# NotSoSmartWatch-BASIC-TOP.net
KiCad netlist of a schematic drawn in EAGLE
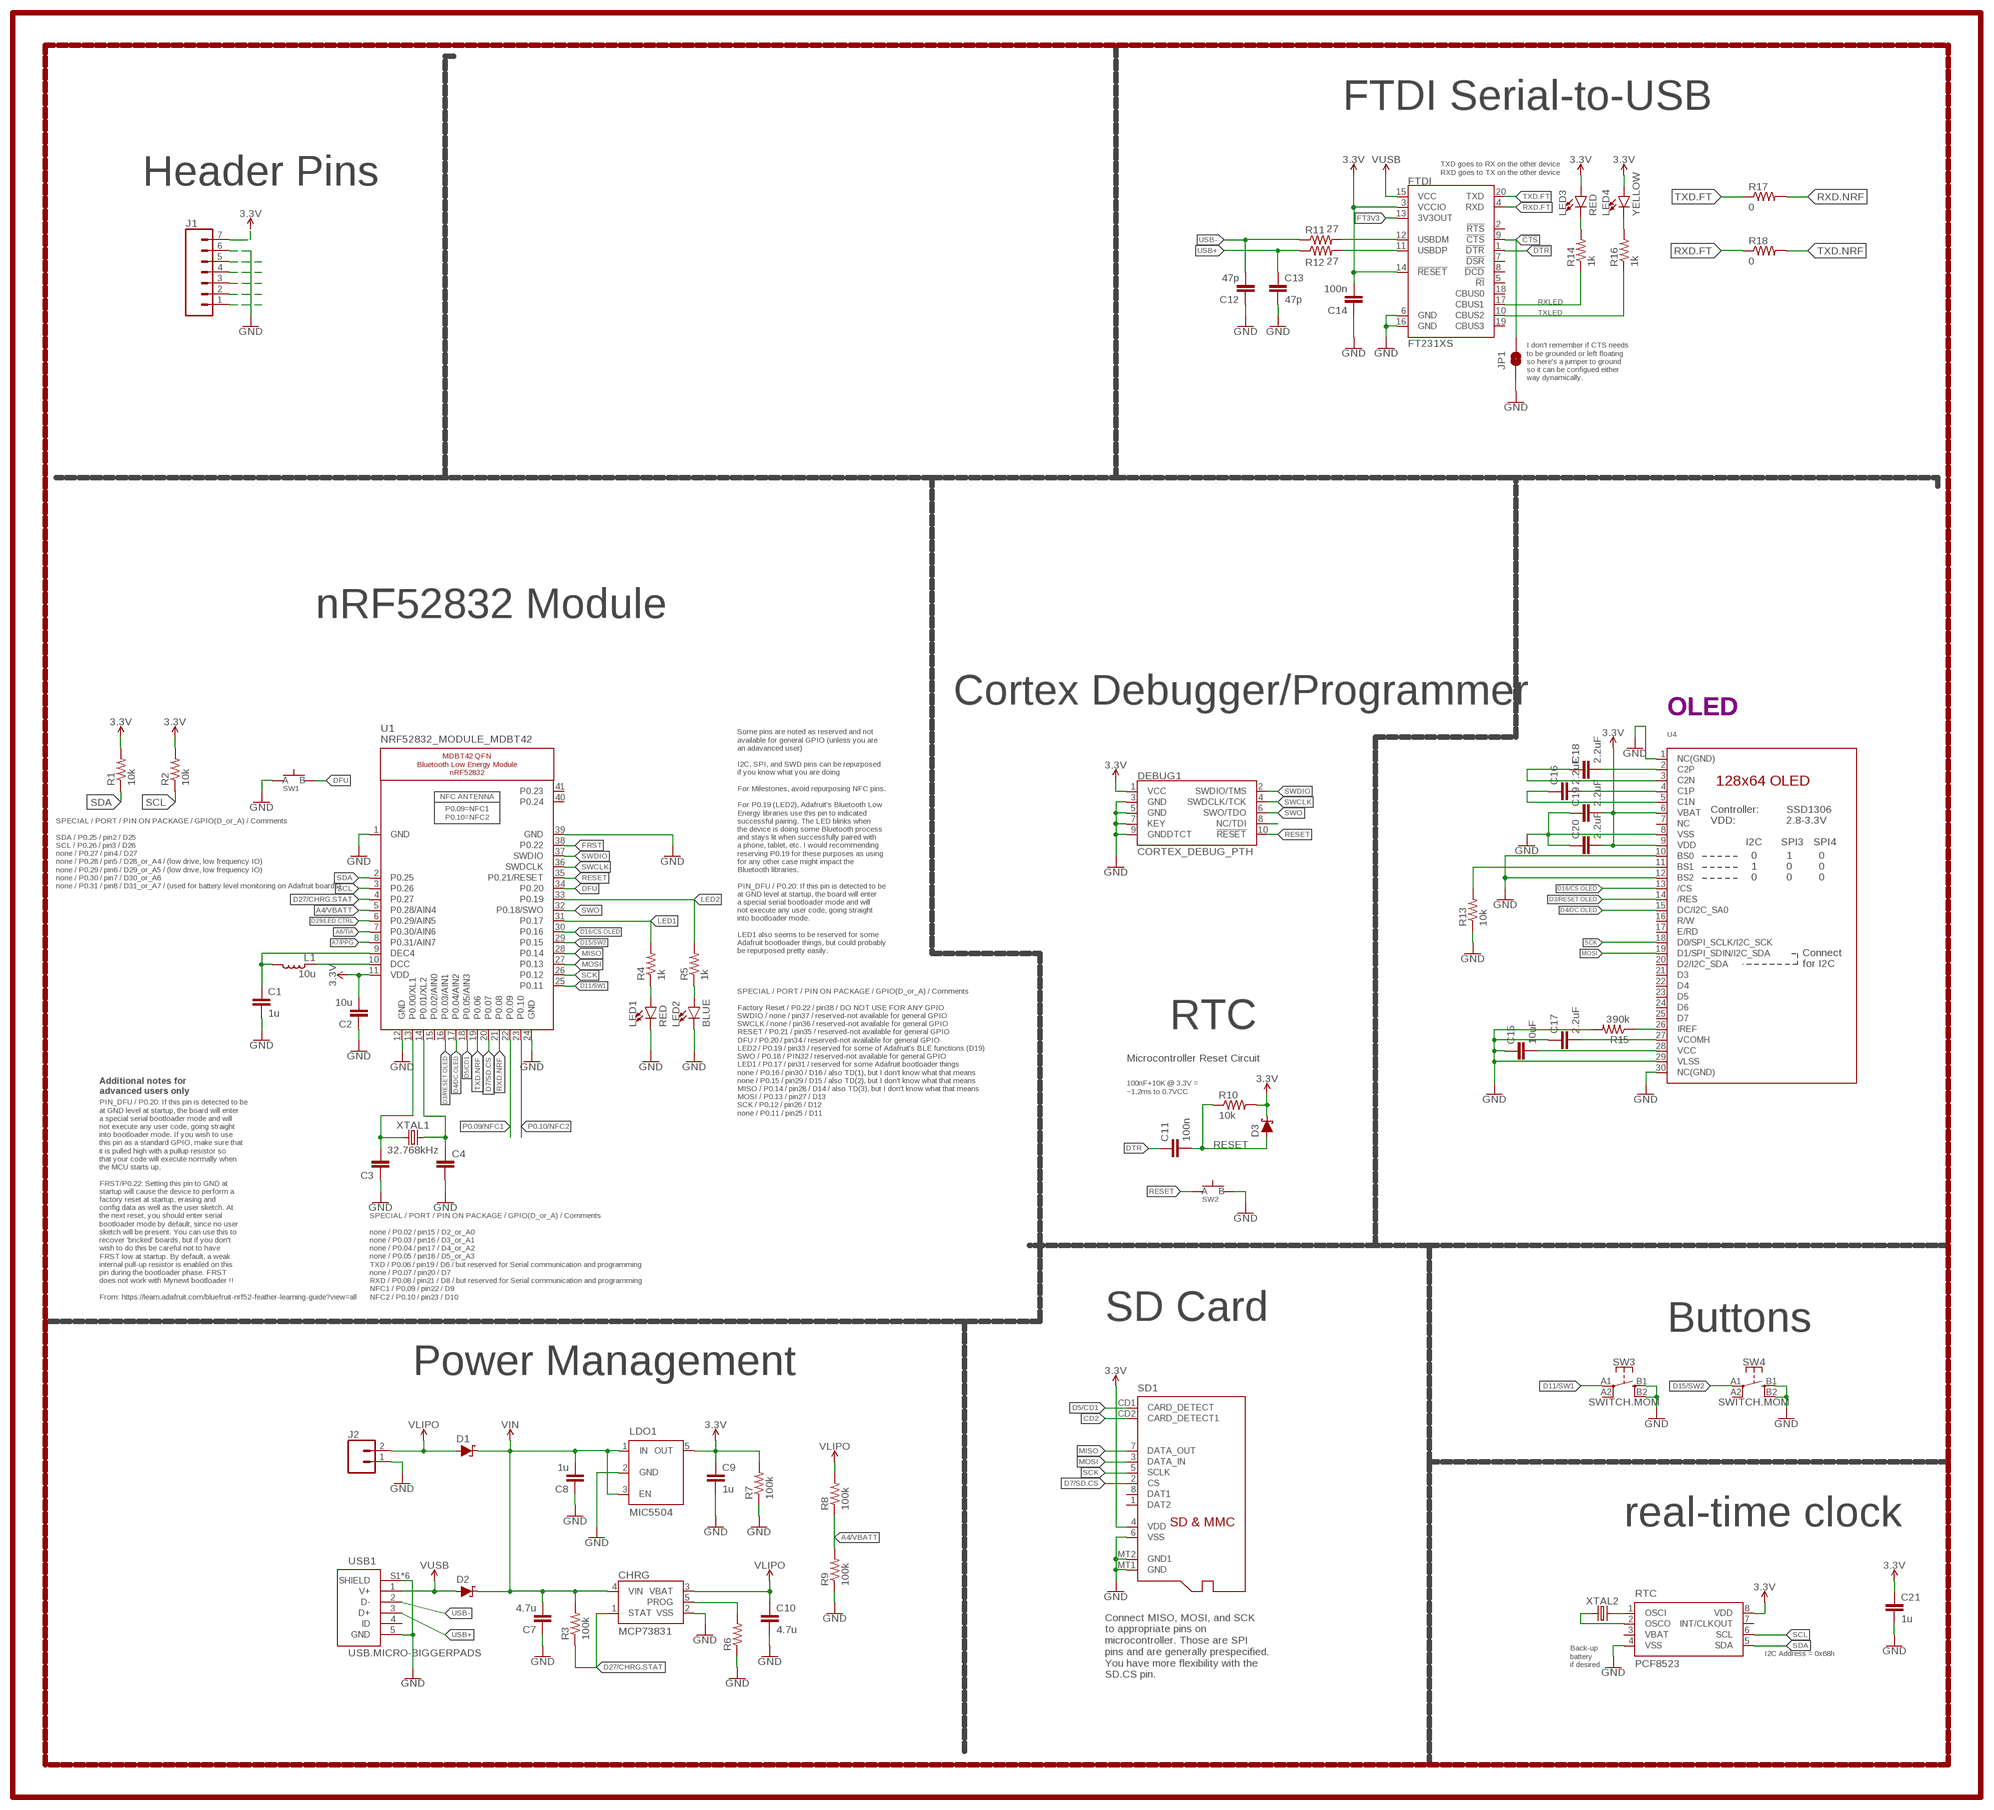
[diagram p0: schematic, sheet 1]

(export (version "E")
  (design (tool "Eeschema 10.0.6"))
  (components
    (comp (ref "C1")
      (value "1u")
      (footprint "eagle-import:C0603")
      (libsource (lib "eagle-import") (part "CAPACITOR0603"))
    )
    (comp (ref "C2")
      (value "10u")
      (footprint "eagle-import:C0805")
      (libsource (lib "eagle-import") (part "CAPACITOR0805"))
    )
    (comp (ref "C3")
      (value "CAPACITOR0603")
      (footprint "eagle-import:C0603")
      (libsource (lib "eagle-import") (part "CAPACITOR0603"))
    )
    (comp (ref "C4")
      (value "CAPACITOR0603")
      (footprint "eagle-import:C0603")
      (libsource (lib "eagle-import") (part "CAPACITOR0603"))
    )
    (comp (ref "C7")
      (value "4.7u")
      (footprint "eagle-import:C0603")
      (libsource (lib "eagle-import") (part "CAPACITOR0603"))
    )
    (comp (ref "C8")
      (value "1u")
      (footprint "eagle-import:C0603")
      (libsource (lib "eagle-import") (part "CAPACITOR0603"))
    )
    (comp (ref "C9")
      (value "1u")
      (footprint "eagle-import:C0603")
      (libsource (lib "eagle-import") (part "CAPACITOR0603"))
    )
    (comp (ref "C10")
      (value "4.7u")
      (footprint "eagle-import:C0603")
      (libsource (lib "eagle-import") (part "CAPACITOR0603"))
    )
    (comp (ref "C11")
      (value "100n")
      (footprint "eagle-import:C0603")
      (libsource (lib "eagle-import") (part "CAPACITOR0603"))
    )
    (comp (ref "C12")
      (value "47p")
      (footprint "eagle-import:C0603")
      (fields (field (name "SPICEPREFIX") "C"))
      (libsource (lib "eagle-import") (part "CAPACITOR0603"))
    )
    (comp (ref "C13")
      (value "47p")
      (footprint "eagle-import:C0603")
      (fields (field (name "SPICEPREFIX") "C"))
      (libsource (lib "eagle-import") (part "CAPACITOR0603"))
    )
    (comp (ref "C14")
      (value "100n")
      (footprint "eagle-import:C0603")
      (fields (field (name "SPICEPREFIX") "C"))
      (libsource (lib "eagle-import") (part "CAPACITOR0603"))
    )
    (comp (ref "C15")
      (value "10uF")
      (footprint "eagle-import:C0603")
      (libsource (lib "eagle-import") (part "CAPACITOR0603"))
    )
    (comp (ref "C16")
      (value "2.2uF")
      (footprint "eagle-import:C0402")
      (libsource (lib "eagle-import") (part "CAPACITOR0402"))
    )
    (comp (ref "C17")
      (value "2.2uF")
      (footprint "eagle-import:C0402")
      (libsource (lib "eagle-import") (part "CAPACITOR0402"))
    )
    (comp (ref "C18")
      (value "2.2uF")
      (footprint "eagle-import:C0402")
      (libsource (lib "eagle-import") (part "CAPACITOR0402"))
    )
    (comp (ref "C19")
      (value "2.2uF")
      (footprint "eagle-import:C0402")
      (libsource (lib "eagle-import") (part "CAPACITOR0402"))
    )
    (comp (ref "C20")
      (value "2.2uF")
      (footprint "eagle-import:C0402")
      (libsource (lib "eagle-import") (part "CAPACITOR0402"))
    )
    (comp (ref "C21")
      (value "1u")
      (footprint "eagle-import:C0603")
      (libsource (lib "eagle-import") (part "CAPACITOR0603"))
    )
    (comp (ref "CHRG")
      (value "MCP73831")
      (footprint "eagle-import:SOT23-5")
      (libsource (lib "eagle-import") (part "MCP73831"))
    )
    (comp (ref "D1")
      (value "SCHOTTKY-USC")
      (footprint "eagle-import:USC")
      (libsource (lib "eagle-import") (part "SCHOTTKY-USC"))
    )
    (comp (ref "D2")
      (value "SCHOTTKY-USC")
      (footprint "eagle-import:USC")
      (libsource (lib "eagle-import") (part "SCHOTTKY-USC"))
    )
    (comp (ref "D3")
      (value "SCHOTTKY-USC")
      (footprint "eagle-import:USC")
      (libsource (lib "eagle-import") (part "SCHOTTKY-USC"))
    )
    (comp (ref "DEBUG1")
      (value "CORTEX_DEBUG_PTH")
      (footprint "eagle-import:2X5-PTH-1.27MM")
      (libsource (lib "eagle-import") (part "CORTEX_DEBUG_PTH"))
    )
    (comp (ref "FTDI")
      (value "FT231XS")
      (footprint "eagle-import:SSOP20_L")
      (fields (field (name "SPICEPREFIX") "X"))
      (libsource (lib "eagle-import") (part "FT231XS"))
    )
    (comp (ref "J1")
      (value "CONN_07-1.27MM")
      (footprint "eagle-import:1X07_1.27MM")
      (libsource (lib "eagle-import") (part "CONN_07-1.27MM"))
    )
    (comp (ref "J2")
      (value "CONN_02")
      (footprint "eagle-import:1X02")
      (libsource (lib "eagle-import") (part "CONN_02"))
    )
    (comp (ref "JP1")
      (value "JUMPER-SMT_2_NO_SILK")
      (footprint "eagle-import:SMT-JUMPER_2_NO_SILK")
      (fields (field (name "SPICEPREFIX") "B"))
      (libsource (lib "eagle-import") (part "JUMPER-SMT_2_NO_SILK"))
    )
    (comp (ref "L1")
      (value "10u")
      (footprint "eagle-import:L0603")
      (libsource (lib "eagle-import") (part "INDUCTOR0603"))
    )
    (comp (ref "LDO1")
      (value "MIC5504")
      (footprint "eagle-import:SOT23-5")
      (libsource (lib "eagle-import") (part "MIC5504"))
    )
    (comp (ref "LED1")
      (value "RED")
      (footprint "eagle-import:LED-0603")
      (libsource (lib "eagle-import") (part "LED0603"))
    )
    (comp (ref "LED2")
      (value "BLUE")
      (footprint "eagle-import:LED-0603")
      (libsource (lib "eagle-import") (part "LED0603"))
    )
    (comp (ref "LED3")
      (value "RED")
      (footprint "eagle-import:LED-0603")
      (fields (field (name "SPICEPREFIX") "L"))
      (libsource (lib "eagle-import") (part "LED0603"))
    )
    (comp (ref "LED4")
      (value "YELLOW")
      (footprint "eagle-import:LED-0603")
      (fields (field (name "SPICEPREFIX") "L"))
      (libsource (lib "eagle-import") (part "LED0603"))
    )
    (comp (ref "R1")
      (value "10k")
      (footprint "eagle-import:R0603")
      (libsource (lib "eagle-import") (part "RESISTOR0603"))
    )
    (comp (ref "R2")
      (value "10k")
      (footprint "eagle-import:R0603")
      (libsource (lib "eagle-import") (part "RESISTOR0603"))
    )
    (comp (ref "R3")
      (value "100k")
      (footprint "eagle-import:R0603")
      (libsource (lib "eagle-import") (part "RESISTOR0603"))
    )
    (comp (ref "R4")
      (value "1k")
      (footprint "eagle-import:R0603")
      (libsource (lib "eagle-import") (part "RESISTOR0603"))
    )
    (comp (ref "R5")
      (value "1k")
      (footprint "eagle-import:R0603")
      (libsource (lib "eagle-import") (part "RESISTOR0603"))
    )
    (comp (ref "R6")
      (value "RESISTOR0603")
      (footprint "eagle-import:R0603")
      (libsource (lib "eagle-import") (part "RESISTOR0603"))
    )
    (comp (ref "R7")
      (value "100k")
      (footprint "eagle-import:R0603")
      (libsource (lib "eagle-import") (part "RESISTOR0603"))
    )
    (comp (ref "R8")
      (value "100k")
      (footprint "eagle-import:R0603")
      (libsource (lib "eagle-import") (part "RESISTOR0603"))
    )
    (comp (ref "R9")
      (value "100k")
      (footprint "eagle-import:R0603")
      (libsource (lib "eagle-import") (part "RESISTOR0603"))
    )
    (comp (ref "R10")
      (value "10k")
      (footprint "eagle-import:R0603")
      (libsource (lib "eagle-import") (part "RESISTOR0603"))
    )
    (comp (ref "R11")
      (value "27")
      (footprint "eagle-import:R0603")
      (fields (field (name "SPICEPREFIX") "R"))
      (libsource (lib "eagle-import") (part "RESISTOR0603"))
    )
    (comp (ref "R12")
      (value "27")
      (footprint "eagle-import:R0603")
      (fields (field (name "SPICEPREFIX") "R"))
      (libsource (lib "eagle-import") (part "RESISTOR0603"))
    )
    (comp (ref "R13")
      (value "10k")
      (footprint "eagle-import:R0603")
      (libsource (lib "eagle-import") (part "RESISTOR0603"))
    )
    (comp (ref "R14")
      (value "1k")
      (footprint "eagle-import:R0603")
      (fields (field (name "SPICEPREFIX") "R"))
      (libsource (lib "eagle-import") (part "RESISTOR0603"))
    )
    (comp (ref "R15")
      (value "390k")
      (footprint "eagle-import:R0603")
      (libsource (lib "eagle-import") (part "RESISTOR0603"))
    )
    (comp (ref "R16")
      (value "1k")
      (footprint "eagle-import:R0603")
      (fields (field (name "SPICEPREFIX") "R"))
      (libsource (lib "eagle-import") (part "RESISTOR0603"))
    )
    (comp (ref "R17")
      (value "0")
      (footprint "eagle-import:R0603")
      (libsource (lib "eagle-import") (part "RESISTOR0603"))
    )
    (comp (ref "R18")
      (value "0")
      (footprint "eagle-import:R0603")
      (libsource (lib "eagle-import") (part "RESISTOR0603"))
    )
    (comp (ref "RTC")
      (value "PCF8523")
      (footprint "eagle-import:SO8")
      (libsource (lib "eagle-import") (part "PCF8523"))
    )
    (comp (ref "SD1")
      (value "MICROSD")
      (footprint "eagle-import:MICROSD")
      (libsource (lib "eagle-import") (part "MICROSD"))
    )
    (comp (ref "SW1")
      (value "SPST-PTS830GG140-COPY.1-3")
      (footprint "eagle-import:BUTTON-GULLWING")
      (libsource (lib "eagle-import") (part "SPST-PTS830GG140-COPY.1-3"))
    )
    (comp (ref "SW2")
      (value "SPST-PTS830GG140-COPY.1-3")
      (footprint "eagle-import:BUTTON-GULLWING")
      (libsource (lib "eagle-import") (part "SPST-PTS830GG140-COPY.1-3"))
    )
    (comp (ref "SW3")
      (value "SWITCH.MOM")
      (footprint "eagle-import:TACTILE_SWITCH_SMD_6.2MM_TALL")
      (libsource (lib "eagle-import") (part "SWITCH.MOM"))
    )
    (comp (ref "SW4")
      (value "SWITCH.MOM")
      (footprint "eagle-import:TACTILE_SWITCH_SMD_6.2MM_TALL")
      (libsource (lib "eagle-import") (part "SWITCH.MOM"))
    )
    (comp (ref "U1")
      (value "NRF52832_MODULE_MDBT42")
      (footprint "eagle-import:BLE_MODULE_RAYTAC_MDBT42")
      (libsource (lib "eagle-import") (part "NRF52832_MODULE_MDBT42"))
    )
    (comp (ref "U4")
      (value "DISP_OLED_UG-2864HSWEG01-NO-WRAPAROUND")
      (footprint "eagle-import:UG-2864HSWEG01_0.96IN_NO-WRAPAROUND")
      (libsource (lib "eagle-import") (part "DISP_OLED_UG-2864HSWEG01-NO-WRAPAROUND"))
    )
    (comp (ref "USB1")
      (value "USB.MICRO-BIGGERPADS")
      (footprint "eagle-import:USB-MICRO-01.BIGGERPADS")
      (libsource (lib "eagle-import") (part "USB.MICRO-BIGGERPADS"))
    )
    (comp (ref "XTAL1")
      (value "32.768kHz")
      (footprint "eagle-import:2-SMD.NOLEAD.2.0MMTO1.2MM")
      (libsource (lib "eagle-import") (part "CRYSTALECS-.327-12.5-12-C-TR"))
    )
    (comp (ref "XTAL2")
      (value "32.7680kHz")
      (footprint "eagle-import:2-SMD.NOLEAD.2.0MMTO1.2MM")
      (fields (field (name "FREQ") "32.7680KHZ"))
      (libsource (lib "eagle-import") (part "CRYSTALECS-.327-12.5-12-C-TR"))
    )
  )
  (nets
    (net (code "1") (name "/RXLED") (class "Default")
      (node (ref "FTDI") (pin "17") (pinfunction "CBUS1_17") (pintype "bidirectional"))
      (node (ref "R14") (pin "1") (pinfunction "1_1") (pintype "passive"))
    )
    (net (code "2") (name "/TXLED") (class "Default")
      (node (ref "FTDI") (pin "10") (pinfunction "CBUS2_10") (pintype "bidirectional"))
      (node (ref "R16") (pin "1") (pinfunction "1_1") (pintype "passive"))
    )
    (net (code "3") (name "/VBAT") (class "Default")
      (node (ref "RTC") (pin "3") (pinfunction "VBAT_3") (pintype "power_in"))
    )
    (net (code "4") (name "/~{CTS}") (class "Default")
      (node (ref "FTDI") (pin "9") (pinfunction "~{CTS}_9") (pintype "bidirectional"))
      (node (ref "JP1") (pin "2") (pinfunction "2_2") (pintype "passive"))
    )
    (net (code "5") (name "/~{DTR}") (class "Default")
      (node (ref "FTDI") (pin "1") (pinfunction "~{DTR}_1") (pintype "bidirectional"))
    )
    (net (code "6") (name "3.3V") (class "Default")
      (node (ref "C14") (pin "2") (pinfunction "2_2") (pintype "passive"))
      (node (ref "C19") (pin "2") (pinfunction "2_2") (pintype "passive"))
      (node (ref "C2") (pin "2") (pinfunction "2_2") (pintype "passive"))
      (node (ref "C20") (pin "2") (pinfunction "2_2") (pintype "passive"))
      (node (ref "C21") (pin "1") (pinfunction "1_1") (pintype "passive"))
      (node (ref "C9") (pin "1") (pinfunction "1_1") (pintype "passive"))
      (node (ref "D3") (pin "-") (pinfunction "C_-") (pintype "passive"))
      (node (ref "DEBUG1") (pin "1") (pinfunction "VCC_1") (pintype "bidirectional"))
      (node (ref "FTDI") (pin "14") (pinfunction "~{RESET}_14") (pintype "bidirectional"))
      (node (ref "FTDI") (pin "3") (pinfunction "VCCIO_3") (pintype "bidirectional"))
      (node (ref "J1") (pin "7") (pinfunction "7_7") (pintype "passive"))
      (node (ref "LDO1") (pin "5") (pinfunction "OUT_5") (pintype "bidirectional"))
      (node (ref "LED3") (pin "A") (pinfunction "A_A") (pintype "passive"))
      (node (ref "LED4") (pin "A") (pinfunction "A_A") (pintype "passive"))
      (node (ref "R1") (pin "2") (pinfunction "2_2") (pintype "passive"))
      (node (ref "R10") (pin "2") (pinfunction "2_2") (pintype "passive"))
      (node (ref "R2") (pin "2") (pinfunction "2_2") (pintype "passive"))
      (node (ref "R7") (pin "2") (pinfunction "2_2") (pintype "passive"))
      (node (ref "RTC") (pin "8") (pinfunction "VDD_8") (pintype "power_in"))
      (node (ref "SD1") (pin "4") (pinfunction "VDD_4") (pintype "power_in"))
      (node (ref "U1") (pin "11") (pinfunction "VDD_11") (pintype "bidirectional"))
      (node (ref "U4") (pin "6") (pinfunction "VBAT_6") (pintype "input"))
      (node (ref "U4") (pin "9") (pinfunction "VDD_9") (pintype "power_in"))
    )
    (net (code "7") (name "A4{slash}VBATT") (class "Default")
      (node (ref "R8") (pin "1") (pinfunction "1_1") (pintype "passive"))
      (node (ref "R9") (pin "2") (pinfunction "2_2") (pintype "passive"))
      (node (ref "U1") (pin "5") (pinfunction "P0.28/AIN4_5") (pintype "bidirectional"))
    )
    (net (code "8") (name "A6{slash}TIA") (class "Default")
      (node (ref "U1") (pin "7") (pinfunction "P0.30/AIN6_7") (pintype "bidirectional"))
    )
    (net (code "9") (name "A7{slash}PPG") (class "Default")
      (node (ref "U1") (pin "8") (pinfunction "P0.31/AIN7_8") (pintype "bidirectional"))
    )
    (net (code "10") (name "CD2") (class "Default")
      (node (ref "SD1") (pin "CD2") (pinfunction "CARD_DETECT1_CD2") (pintype "passive"))
    )
    (net (code "11") (name "D3{slash}RESET.OLED") (class "Default")
      (node (ref "U1") (pin "16") (pinfunction "P0.03/AIN1_16") (pintype "bidirectional"))
      (node (ref "U4") (pin "14") (pinfunction "/RES_14") (pintype "input"))
    )
    (net (code "12") (name "D4{slash}DC.OLED") (class "Default")
      (node (ref "U1") (pin "17") (pinfunction "P0.04/AIN2_17") (pintype "bidirectional"))
      (node (ref "U4") (pin "15") (pinfunction "DC/I2C_SA0_15") (pintype "input"))
    )
    (net (code "13") (name "D5{slash}CD1") (class "Default")
      (node (ref "SD1") (pin "CD1") (pinfunction "CARD_DETECT_CD1") (pintype "passive"))
      (node (ref "U1") (pin "18") (pinfunction "P0.05/AIN3_18") (pintype "bidirectional"))
    )
    (net (code "14") (name "D7{slash}SD.CS") (class "Default")
      (node (ref "SD1") (pin "2") (pinfunction "CS_2") (pintype "input"))
      (node (ref "U1") (pin "20") (pinfunction "P0.07_20") (pintype "bidirectional"))
    )
    (net (code "15") (name "D11{slash}SW1") (class "Default")
      (node (ref "SW3") (pin "A1") (pinfunction "1_A1") (pintype "passive"))
      (node (ref "U1") (pin "25") (pinfunction "P0.11_25") (pintype "bidirectional"))
    )
    (net (code "16") (name "D15{slash}SW2") (class "Default")
      (node (ref "SW4") (pin "A1") (pinfunction "1_A1") (pintype "passive"))
      (node (ref "U1") (pin "29") (pinfunction "P0.15_29") (pintype "bidirectional"))
    )
    (net (code "17") (name "D16{slash}CS.OLED") (class "Default")
      (node (ref "U1") (pin "30") (pinfunction "P0.16_30") (pintype "bidirectional"))
      (node (ref "U4") (pin "13") (pinfunction "/CS_13") (pintype "input"))
    )
    (net (code "18") (name "D27{slash}CHRG.STAT") (class "Default")
      (node (ref "CHRG") (pin "1") (pinfunction "STAT_1") (pintype "output"))
      (node (ref "R3") (pin "1") (pinfunction "1_1") (pintype "passive"))
      (node (ref "U1") (pin "4") (pinfunction "P0.27_4") (pintype "bidirectional"))
    )
    (net (code "19") (name "D29{slash}LED.CTRL") (class "Default")
      (node (ref "U1") (pin "6") (pinfunction "P0.29/AIN5_6") (pintype "bidirectional"))
    )
    (net (code "20") (name "DFU") (class "Default")
      (node (ref "SW1") (pin "3") (pinfunction "B_3") (pintype "bidirectional"))
      (node (ref "U1") (pin "34") (pinfunction "P0.20_34") (pintype "bidirectional"))
    )
    (net (code "21") (name "DTR") (class "Default")
      (node (ref "C11") (pin "1") (pinfunction "1_1") (pintype "passive"))
    )
    (net (code "22") (name "FRST") (class "Default")
      (node (ref "U1") (pin "38") (pinfunction "P0.22_38") (pintype "bidirectional"))
    )
    (net (code "23") (name "FT3V3") (class "Default")
      (node (ref "FTDI") (pin "13") (pinfunction "3V3OUT_13") (pintype "bidirectional"))
    )
    (net (code "24") (name "GND") (class "Default")
      (node (ref "C1") (pin "2") (pinfunction "2_2") (pintype "passive"))
      (node (ref "C10") (pin "2") (pinfunction "2_2") (pintype "passive"))
      (node (ref "C12") (pin "1") (pinfunction "1_1") (pintype "passive"))
      (node (ref "C13") (pin "2") (pinfunction "2_2") (pintype "passive"))
      (node (ref "C14") (pin "1") (pinfunction "1_1") (pintype "passive"))
      (node (ref "C15") (pin "1") (pinfunction "1_1") (pintype "passive"))
      (node (ref "C17") (pin "1") (pinfunction "1_1") (pintype "passive"))
      (node (ref "C19") (pin "1") (pinfunction "1_1") (pintype "passive"))
      (node (ref "C2") (pin "1") (pinfunction "1_1") (pintype "passive"))
      (node (ref "C20") (pin "1") (pinfunction "1_1") (pintype "passive"))
      (node (ref "C21") (pin "2") (pinfunction "2_2") (pintype "passive"))
      (node (ref "C3") (pin "1") (pinfunction "1_1") (pintype "passive"))
      (node (ref "C4") (pin "2") (pinfunction "2_2") (pintype "passive"))
      (node (ref "C7") (pin "1") (pinfunction "1_1") (pintype "passive"))
      (node (ref "C8") (pin "1") (pinfunction "1_1") (pintype "passive"))
      (node (ref "C9") (pin "2") (pinfunction "2_2") (pintype "passive"))
      (node (ref "CHRG") (pin "2") (pinfunction "VSS_2") (pintype "power_in"))
      (node (ref "DEBUG1") (pin "3") (pinfunction "GND_3") (pintype "bidirectional"))
      (node (ref "DEBUG1") (pin "5") (pinfunction "GND_5") (pintype "bidirectional"))
      (node (ref "DEBUG1") (pin "7") (pinfunction "KEY_7") (pintype "bidirectional"))
      (node (ref "DEBUG1") (pin "9") (pinfunction "GNDDTCT_9") (pintype "bidirectional"))
      (node (ref "FTDI") (pin "16") (pinfunction "GND_16") (pintype "bidirectional"))
      (node (ref "FTDI") (pin "6") (pinfunction "GND_6") (pintype "bidirectional"))
      (node (ref "J1") (pin "6") (pinfunction "6_6") (pintype "passive"))
      (node (ref "J2") (pin "1") (pinfunction "1_1") (pintype "passive"))
      (node (ref "JP1") (pin "1") (pinfunction "1_1") (pintype "passive"))
      (node (ref "LDO1") (pin "2") (pinfunction "GND_2") (pintype "bidirectional"))
      (node (ref "LED1") (pin "C") (pinfunction "C_C") (pintype "passive"))
      (node (ref "LED2") (pin "C") (pinfunction "C_C") (pintype "passive"))
      (node (ref "R13") (pin "1") (pinfunction "1_1") (pintype "passive"))
      (node (ref "R15") (pin "2") (pinfunction "2_2") (pintype "passive"))
      (node (ref "R6") (pin "1") (pinfunction "1_1") (pintype "passive"))
      (node (ref "R7") (pin "1") (pinfunction "1_1") (pintype "passive"))
      (node (ref "R9") (pin "1") (pinfunction "1_1") (pintype "passive"))
      (node (ref "RTC") (pin "4") (pinfunction "VSS_4") (pintype "power_in"))
      (node (ref "SD1") (pin "6") (pinfunction "VSS_6") (pintype "power_in"))
      (node (ref "SD1") (pin "MT1") (pinfunction "GND_MT1") (pintype "power_in"))
      (node (ref "SD1") (pin "MT2") (pinfunction "GND1_MT2") (pintype "power_in"))
      (node (ref "SW1") (pin "1") (pinfunction "A_1") (pintype "bidirectional"))
      (node (ref "SW2") (pin "3") (pinfunction "B_3") (pintype "bidirectional"))
      (node (ref "SW3") (pin "B1") (pinfunction "3_B1") (pintype "passive"))
      (node (ref "SW3") (pin "B2") (pinfunction "4_B2") (pintype "passive"))
      (node (ref "SW4") (pin "B1") (pinfunction "3_B1") (pintype "passive"))
      (node (ref "SW4") (pin "B2") (pinfunction "4_B2") (pintype "passive"))
      (node (ref "U1") (pin "1") (pinfunction "GND_1") (pintype "bidirectional"))
      (node (ref "U1") (pin "12") (pinfunction "GND_12") (pintype "bidirectional"))
      (node (ref "U1") (pin "24") (pinfunction "GND_24") (pintype "bidirectional"))
      (node (ref "U1") (pin "39") (pinfunction "GND_39") (pintype "bidirectional"))
      (node (ref "U4") (pin "1") (pinfunction "NC(GND)_1") (pintype "input"))
      (node (ref "U4") (pin "10") (pinfunction "BS0_10") (pintype "input"))
      (node (ref "U4") (pin "12") (pinfunction "BS2_12") (pintype "input"))
      (node (ref "U4") (pin "29") (pinfunction "VLSS_29") (pintype "power_in"))
      (node (ref "U4") (pin "30") (pinfunction "NC(GND)_30") (pintype "input"))
      (node (ref "U4") (pin "8") (pinfunction "VSS_8") (pintype "power_in"))
      (node (ref "USB1") (pin "5") (pinfunction "GND_5") (pintype "bidirectional"))
      (node (ref "USB1") (pin "S1") (pinfunction "SHIELD_S1") (pintype "bidirectional"))
      (node (ref "USB1") (pin "S2") (pinfunction "SHIELD_S2") (pintype "bidirectional"))
      (node (ref "USB1") (pin "S3") (pinfunction "SHIELD_S3") (pintype "bidirectional"))
      (node (ref "USB1") (pin "S4") (pinfunction "SHIELD_S4") (pintype "bidirectional"))
      (node (ref "USB1") (pin "S5") (pinfunction "SHIELD_S5") (pintype "bidirectional"))
      (node (ref "USB1") (pin "S6") (pinfunction "SHIELD_S6") (pintype "bidirectional"))
    )
    (net (code "25") (name "LED1") (class "Default")
      (node (ref "R4") (pin "2") (pinfunction "2_2") (pintype "passive"))
      (node (ref "U1") (pin "31") (pinfunction "P0.17_31") (pintype "bidirectional"))
    )
    (net (code "26") (name "LED2") (class "Default")
      (node (ref "R5") (pin "2") (pinfunction "2_2") (pintype "passive"))
      (node (ref "U1") (pin "33") (pinfunction "P0.19_33") (pintype "bidirectional"))
    )
    (net (code "27") (name "MISO") (class "Default")
      (node (ref "SD1") (pin "7") (pinfunction "DATA_OUT_7") (pintype "output"))
      (node (ref "U1") (pin "28") (pinfunction "P0.14_28") (pintype "bidirectional"))
    )
    (net (code "28") (name "MOSI") (class "Default")
      (node (ref "SD1") (pin "3") (pinfunction "DATA_IN_3") (pintype "input"))
      (node (ref "U1") (pin "27") (pinfunction "P0.13_27") (pintype "bidirectional"))
      (node (ref "U4") (pin "19") (pinfunction "D1/SPI_SDIN/I2C_SDA_19") (pintype "bidirectional"))
    )
    (net (code "29") (name "Net-(CHRG-PROG)") (class "Default")
      (node (ref "CHRG") (pin "5") (pinfunction "PROG_5") (pintype "input"))
      (node (ref "R6") (pin "2") (pinfunction "2_2") (pintype "passive"))
    )
    (net (code "30") (name "Net-(FTDI-USBDM)") (class "Default")
      (node (ref "FTDI") (pin "12") (pinfunction "USBDM_12") (pintype "bidirectional"))
      (node (ref "R11") (pin "2") (pinfunction "2_2") (pintype "passive"))
    )
    (net (code "31") (name "Net-(FTDI-USBDP)") (class "Default")
      (node (ref "FTDI") (pin "11") (pinfunction "USBDP_11") (pintype "bidirectional"))
      (node (ref "R12") (pin "2") (pinfunction "2_2") (pintype "passive"))
    )
    (net (code "32") (name "Net-(LED1-PadA)") (class "Default")
      (node (ref "LED1") (pin "A") (pinfunction "A_A") (pintype "passive"))
      (node (ref "R4") (pin "1") (pinfunction "1_1") (pintype "passive"))
    )
    (net (code "33") (name "Net-(LED2-PadA)") (class "Default")
      (node (ref "LED2") (pin "A") (pinfunction "A_A") (pintype "passive"))
      (node (ref "R5") (pin "1") (pinfunction "1_1") (pintype "passive"))
    )
    (net (code "34") (name "Net-(LED3-PadC)") (class "Default")
      (node (ref "LED3") (pin "C") (pinfunction "C_C") (pintype "passive"))
      (node (ref "R14") (pin "2") (pinfunction "2_2") (pintype "passive"))
    )
    (net (code "35") (name "Net-(LED4-PadC)") (class "Default")
      (node (ref "LED4") (pin "C") (pinfunction "C_C") (pintype "passive"))
      (node (ref "R16") (pin "2") (pinfunction "2_2") (pintype "passive"))
    )
    (net (code "36") (name "Net-(RTC-OSCI)") (class "Default")
      (node (ref "RTC") (pin "1") (pinfunction "OSCI_1") (pintype "bidirectional"))
      (node (ref "XTAL2") (pin "P$2") (pinfunction "2_P$2") (pintype "passive"))
    )
    (net (code "37") (name "Net-(RTC-OSCO)") (class "Default")
      (node (ref "RTC") (pin "2") (pinfunction "OSCO_2") (pintype "bidirectional"))
      (node (ref "XTAL2") (pin "P$1") (pinfunction "1_P$1") (pintype "passive"))
    )
    (net (code "38") (name "Net-(U1-DCC)") (class "Default")
      (node (ref "L1") (pin "1") (pinfunction "1_1") (pintype "passive"))
      (node (ref "U1") (pin "10") (pinfunction "DCC_10") (pintype "bidirectional"))
    )
    (net (code "39") (name "Net-(U1-DEC4)") (class "Default")
      (node (ref "C1") (pin "1") (pinfunction "1_1") (pintype "passive"))
      (node (ref "L1") (pin "2") (pinfunction "2_2") (pintype "passive"))
      (node (ref "U1") (pin "9") (pinfunction "DEC4_9") (pintype "bidirectional"))
    )
    (net (code "40") (name "Net-(U1-P0.00{slash}XL1)") (class "Default")
      (node (ref "C3") (pin "2") (pinfunction "2_2") (pintype "passive"))
      (node (ref "U1") (pin "13") (pinfunction "P0.00/XL1_13") (pintype "bidirectional"))
      (node (ref "XTAL1") (pin "P$1") (pinfunction "1_P$1") (pintype "passive"))
    )
    (net (code "41") (name "Net-(U1-P0.01{slash}XL2)") (class "Default")
      (node (ref "C4") (pin "1") (pinfunction "1_1") (pintype "passive"))
      (node (ref "U1") (pin "14") (pinfunction "P0.01/XL2_14") (pintype "bidirectional"))
      (node (ref "XTAL1") (pin "P$2") (pinfunction "2_P$2") (pintype "passive"))
    )
    (net (code "42") (name "Net-(U4-BS1)") (class "Default")
      (node (ref "R13") (pin "2") (pinfunction "2_2") (pintype "passive"))
      (node (ref "U4") (pin "11") (pinfunction "BS1_11") (pintype "input"))
    )
    (net (code "43") (name "Net-(U4-C1N)") (class "Default")
      (node (ref "C16") (pin "1") (pinfunction "1_1") (pintype "passive"))
      (node (ref "U4") (pin "5") (pinfunction "C1N_5") (pintype "input"))
    )
    (net (code "44") (name "Net-(U4-C1P)") (class "Default")
      (node (ref "C16") (pin "2") (pinfunction "2_2") (pintype "passive"))
      (node (ref "U4") (pin "4") (pinfunction "C1P_4") (pintype "input"))
    )
    (net (code "45") (name "Net-(U4-C2N)") (class "Default")
      (node (ref "C18") (pin "1") (pinfunction "1_1") (pintype "passive"))
      (node (ref "U4") (pin "3") (pinfunction "C2N_3") (pintype "input"))
    )
    (net (code "46") (name "Net-(U4-C2P)") (class "Default")
      (node (ref "C18") (pin "2") (pinfunction "2_2") (pintype "passive"))
      (node (ref "U4") (pin "2") (pinfunction "C2P_2") (pintype "input"))
    )
    (net (code "47") (name "Net-(U4-IREF)") (class "Default")
      (node (ref "R15") (pin "1") (pinfunction "1_1") (pintype "passive"))
      (node (ref "U4") (pin "26") (pinfunction "IREF_26") (pintype "input"))
    )
    (net (code "48") (name "Net-(U4-VCC)") (class "Default")
      (node (ref "C15") (pin "2") (pinfunction "2_2") (pintype "passive"))
      (node (ref "U4") (pin "28") (pinfunction "VCC_28") (pintype "power_in"))
    )
    (net (code "49") (name "Net-(U4-VCOMH)") (class "Default")
      (node (ref "C17") (pin "2") (pinfunction "2_2") (pintype "passive"))
      (node (ref "U4") (pin "27") (pinfunction "VCOMH_27") (pintype "output"))
    )
    (net (code "50") (name "P0.09{slash}NFC1") (class "Default")
      (node (ref "U1") (pin "22") (pinfunction "P0.09_22") (pintype "bidirectional"))
    )
    (net (code "51") (name "P0.10{slash}NFC2") (class "Default")
      (node (ref "U1") (pin "23") (pinfunction "P0.10_23") (pintype "bidirectional"))
    )
    (net (code "52") (name "RESET") (class "Default")
      (node (ref "C11") (pin "2") (pinfunction "2_2") (pintype "passive"))
      (node (ref "D3") (pin "+") (pinfunction "A_+") (pintype "passive"))
      (node (ref "DEBUG1") (pin "10") (pinfunction "~{RESET}_10") (pintype "bidirectional"))
      (node (ref "R10") (pin "1") (pinfunction "1_1") (pintype "passive"))
      (node (ref "SW2") (pin "1") (pinfunction "A_1") (pintype "bidirectional"))
      (node (ref "U1") (pin "35") (pinfunction "P0.21/RESET_35") (pintype "bidirectional"))
    )
    (net (code "53") (name "RXD.FT") (class "Default")
      (node (ref "FTDI") (pin "4") (pinfunction "RXD_4") (pintype "bidirectional"))
      (node (ref "R18") (pin "1") (pinfunction "1_1") (pintype "passive"))
    )
    (net (code "54") (name "RXD.NRF") (class "Default")
      (node (ref "R17") (pin "2") (pinfunction "2_2") (pintype "passive"))
      (node (ref "U1") (pin "21") (pinfunction "P0.08_21") (pintype "bidirectional"))
    )
    (net (code "55") (name "SCK") (class "Default")
      (node (ref "SD1") (pin "5") (pinfunction "SCLK_5") (pintype "input"))
      (node (ref "U1") (pin "26") (pinfunction "P0.12_26") (pintype "bidirectional"))
      (node (ref "U4") (pin "18") (pinfunction "D0/SPI_SCLK/I2C_SCK_18") (pintype "bidirectional"))
    )
    (net (code "56") (name "SCL") (class "Default")
      (node (ref "R2") (pin "1") (pinfunction "1_1") (pintype "passive"))
      (node (ref "RTC") (pin "6") (pinfunction "SCL_6") (pintype "bidirectional"))
      (node (ref "U1") (pin "3") (pinfunction "P0.26_3") (pintype "bidirectional"))
    )
    (net (code "57") (name "SDA") (class "Default")
      (node (ref "R1") (pin "1") (pinfunction "1_1") (pintype "passive"))
      (node (ref "RTC") (pin "5") (pinfunction "SDA_5") (pintype "bidirectional"))
      (node (ref "U1") (pin "2") (pinfunction "P0.25_2") (pintype "bidirectional"))
    )
    (net (code "58") (name "SWCLK") (class "Default")
      (node (ref "DEBUG1") (pin "4") (pinfunction "SWDCLK/TCK_4") (pintype "bidirectional"))
      (node (ref "U1") (pin "36") (pinfunction "SWDCLK_36") (pintype "bidirectional"))
    )
    (net (code "59") (name "SWDIO") (class "Default")
      (node (ref "DEBUG1") (pin "2") (pinfunction "SWDIO/TMS_2") (pintype "bidirectional"))
      (node (ref "U1") (pin "37") (pinfunction "SWDIO_37") (pintype "bidirectional"))
    )
    (net (code "60") (name "SWO") (class "Default")
      (node (ref "DEBUG1") (pin "6") (pinfunction "SWO/TDO_6") (pintype "bidirectional"))
      (node (ref "U1") (pin "32") (pinfunction "P0.18/SWO_32") (pintype "bidirectional"))
    )
    (net (code "61") (name "TXD.FT") (class "Default")
      (node (ref "FTDI") (pin "20") (pinfunction "TXD_20") (pintype "bidirectional"))
      (node (ref "R17") (pin "1") (pinfunction "1_1") (pintype "passive"))
    )
    (net (code "62") (name "TXD.NRF") (class "Default")
      (node (ref "R18") (pin "2") (pinfunction "2_2") (pintype "passive"))
      (node (ref "U1") (pin "19") (pinfunction "P0.06_19") (pintype "bidirectional"))
    )
    (net (code "63") (name "USB+") (class "Default")
      (node (ref "C13") (pin "1") (pinfunction "1_1") (pintype "passive"))
      (node (ref "R12") (pin "1") (pinfunction "1_1") (pintype "passive"))
      (node (ref "USB1") (pin "3") (pinfunction "D+_3") (pintype "bidirectional"))
    )
    (net (code "64") (name "USB-") (class "Default")
      (node (ref "C12") (pin "2") (pinfunction "2_2") (pintype "passive"))
      (node (ref "R11") (pin "1") (pinfunction "1_1") (pintype "passive"))
      (node (ref "USB1") (pin "2") (pinfunction "D-_2") (pintype "bidirectional"))
    )
    (net (code "65") (name "VIN") (class "Default")
      (node (ref "C7") (pin "2") (pinfunction "2_2") (pintype "passive"))
      (node (ref "C8") (pin "2") (pinfunction "2_2") (pintype "passive"))
      (node (ref "CHRG") (pin "4") (pinfunction "VIN_4") (pintype "power_in"))
      (node (ref "D1") (pin "-") (pinfunction "C_-") (pintype "passive"))
      (node (ref "D2") (pin "-") (pinfunction "C_-") (pintype "passive"))
      (node (ref "LDO1") (pin "1") (pinfunction "IN_1") (pintype "bidirectional"))
      (node (ref "LDO1") (pin "3") (pinfunction "EN_3") (pintype "bidirectional"))
      (node (ref "R3") (pin "2") (pinfunction "2_2") (pintype "passive"))
    )
    (net (code "66") (name "VLIPO") (class "Default")
      (node (ref "C10") (pin "1") (pinfunction "1_1") (pintype "passive"))
      (node (ref "CHRG") (pin "3") (pinfunction "VBAT_3") (pintype "power_in"))
      (node (ref "D1") (pin "+") (pinfunction "A_+") (pintype "passive"))
      (node (ref "J2") (pin "2") (pinfunction "2_2") (pintype "passive"))
      (node (ref "R8") (pin "2") (pinfunction "2_2") (pintype "passive"))
    )
    (net (code "67") (name "VUSB") (class "Default")
      (node (ref "D2") (pin "+") (pinfunction "A_+") (pintype "passive"))
      (node (ref "FTDI") (pin "15") (pinfunction "VCC_15") (pintype "bidirectional"))
      (node (ref "USB1") (pin "1") (pinfunction "V+_1") (pintype "bidirectional"))
    )
    (net (code "68") (name "unconnected-(DEBUG1-NC{slash}TDI-Pad8)") (class "Default")
      (node (ref "DEBUG1") (pin "8") (pinfunction "NC/TDI_8") (pintype "bidirectional"))
    )
    (net (code "69") (name "unconnected-(FTDI-CBUS0-Pad18)") (class "Default")
      (node (ref "FTDI") (pin "18") (pinfunction "CBUS0_18") (pintype "bidirectional"))
    )
    (net (code "70") (name "unconnected-(FTDI-CBUS3-Pad19)") (class "Default")
      (node (ref "FTDI") (pin "19") (pinfunction "CBUS3_19") (pintype "bidirectional"))
    )
    (net (code "71") (name "unconnected-(FTDI-~{DCD}-Pad8)") (class "Default")
      (node (ref "FTDI") (pin "8") (pinfunction "~{DCD}_8") (pintype "bidirectional"))
    )
    (net (code "72") (name "unconnected-(FTDI-~{DSR}-Pad7)") (class "Default")
      (node (ref "FTDI") (pin "7") (pinfunction "~{DSR}_7") (pintype "bidirectional"))
    )
    (net (code "73") (name "unconnected-(FTDI-~{RI}-Pad5)") (class "Default")
      (node (ref "FTDI") (pin "5") (pinfunction "~{RI}_5") (pintype "bidirectional"))
    )
    (net (code "74") (name "unconnected-(FTDI-~{RTS}-Pad2)") (class "Default")
      (node (ref "FTDI") (pin "2") (pinfunction "~{RTS}_2") (pintype "bidirectional"))
    )
    (net (code "75") (name "unconnected-(J1-Pad1)") (class "Default")
      (node (ref "J1") (pin "1") (pinfunction "1_1") (pintype "passive"))
    )
    (net (code "76") (name "unconnected-(J1-Pad2)") (class "Default")
      (node (ref "J1") (pin "2") (pinfunction "2_2") (pintype "passive"))
    )
    (net (code "77") (name "unconnected-(J1-Pad3)") (class "Default")
      (node (ref "J1") (pin "3") (pinfunction "3_3") (pintype "passive"))
    )
    (net (code "78") (name "unconnected-(J1-Pad4)") (class "Default")
      (node (ref "J1") (pin "4") (pinfunction "4_4") (pintype "passive"))
    )
    (net (code "79") (name "unconnected-(J1-Pad5)") (class "Default")
      (node (ref "J1") (pin "5") (pinfunction "5_5") (pintype "passive"))
    )
    (net (code "80") (name "unconnected-(RTC-INT{slash}CLKOUT-Pad7)") (class "Default")
      (node (ref "RTC") (pin "7") (pinfunction "INT/CLKOUT_7") (pintype "bidirectional"))
    )
    (net (code "81") (name "unconnected-(SD1-DAT1-Pad8)") (class "Default")
      (node (ref "SD1") (pin "8") (pinfunction "DAT1_8") (pintype "bidirectional"))
    )
    (net (code "82") (name "unconnected-(SD1-DAT2-Pad1)") (class "Default")
      (node (ref "SD1") (pin "1") (pinfunction "DAT2_1") (pintype "bidirectional"))
    )
    (net (code "83") (name "unconnected-(SW3-2-PadA2)") (class "Default")
      (node (ref "SW3") (pin "A2") (pinfunction "2_A2") (pintype "passive"))
    )
    (net (code "84") (name "unconnected-(SW4-2-PadA2)") (class "Default")
      (node (ref "SW4") (pin "A2") (pinfunction "2_A2") (pintype "passive"))
    )
    (net (code "85") (name "unconnected-(U1-P0.02{slash}AIN0-Pad15)") (class "Default")
      (node (ref "U1") (pin "15") (pinfunction "P0.02/AIN0_15") (pintype "bidirectional"))
    )
    (net (code "86") (name "unconnected-(U1-P0.23-Pad41)") (class "Default")
      (node (ref "U1") (pin "41") (pinfunction "P0.23_41") (pintype "bidirectional"))
    )
    (net (code "87") (name "unconnected-(U1-P0.24-Pad40)") (class "Default")
      (node (ref "U1") (pin "40") (pinfunction "P0.24_40") (pintype "bidirectional"))
    )
    (net (code "88") (name "unconnected-(U4-D2{slash}I2C_SDA-Pad20)") (class "Default")
      (node (ref "U4") (pin "20") (pinfunction "D2/I2C_SDA_20") (pintype "bidirectional"))
    )
    (net (code "89") (name "unconnected-(U4-D3-Pad21)") (class "Default")
      (node (ref "U4") (pin "21") (pinfunction "D3_21") (pintype "bidirectional"))
    )
    (net (code "90") (name "unconnected-(U4-D4-Pad22)") (class "Default")
      (node (ref "U4") (pin "22") (pinfunction "D4_22") (pintype "bidirectional"))
    )
    (net (code "91") (name "unconnected-(U4-D5-Pad23)") (class "Default")
      (node (ref "U4") (pin "23") (pinfunction "D5_23") (pintype "bidirectional"))
    )
    (net (code "92") (name "unconnected-(U4-D6-Pad24)") (class "Default")
      (node (ref "U4") (pin "24") (pinfunction "D6_24") (pintype "bidirectional"))
    )
    (net (code "93") (name "unconnected-(U4-D7-Pad25)") (class "Default")
      (node (ref "U4") (pin "25") (pinfunction "D7_25") (pintype "bidirectional"))
    )
    (net (code "94") (name "unconnected-(U4-E{slash}RD-Pad17)") (class "Default")
      (node (ref "U4") (pin "17") (pinfunction "E/RD_17") (pintype "input"))
    )
    (net (code "95") (name "unconnected-(U4-NC-Pad7)") (class "Default")
      (node (ref "U4") (pin "7") (pinfunction "NC_7") (pintype "no_connect"))
    )
    (net (code "96") (name "unconnected-(U4-R{slash}W-Pad16)") (class "Default")
      (node (ref "U4") (pin "16") (pinfunction "R/W_16") (pintype "input"))
    )
    (net (code "97") (name "unconnected-(USB1-ID-Pad4)") (class "Default")
      (node (ref "USB1") (pin "4") (pinfunction "ID_4") (pintype "bidirectional"))
    )
  )
)
